# Sheet1.net
KiCad netlist of a schematic drawn in Altium Designer
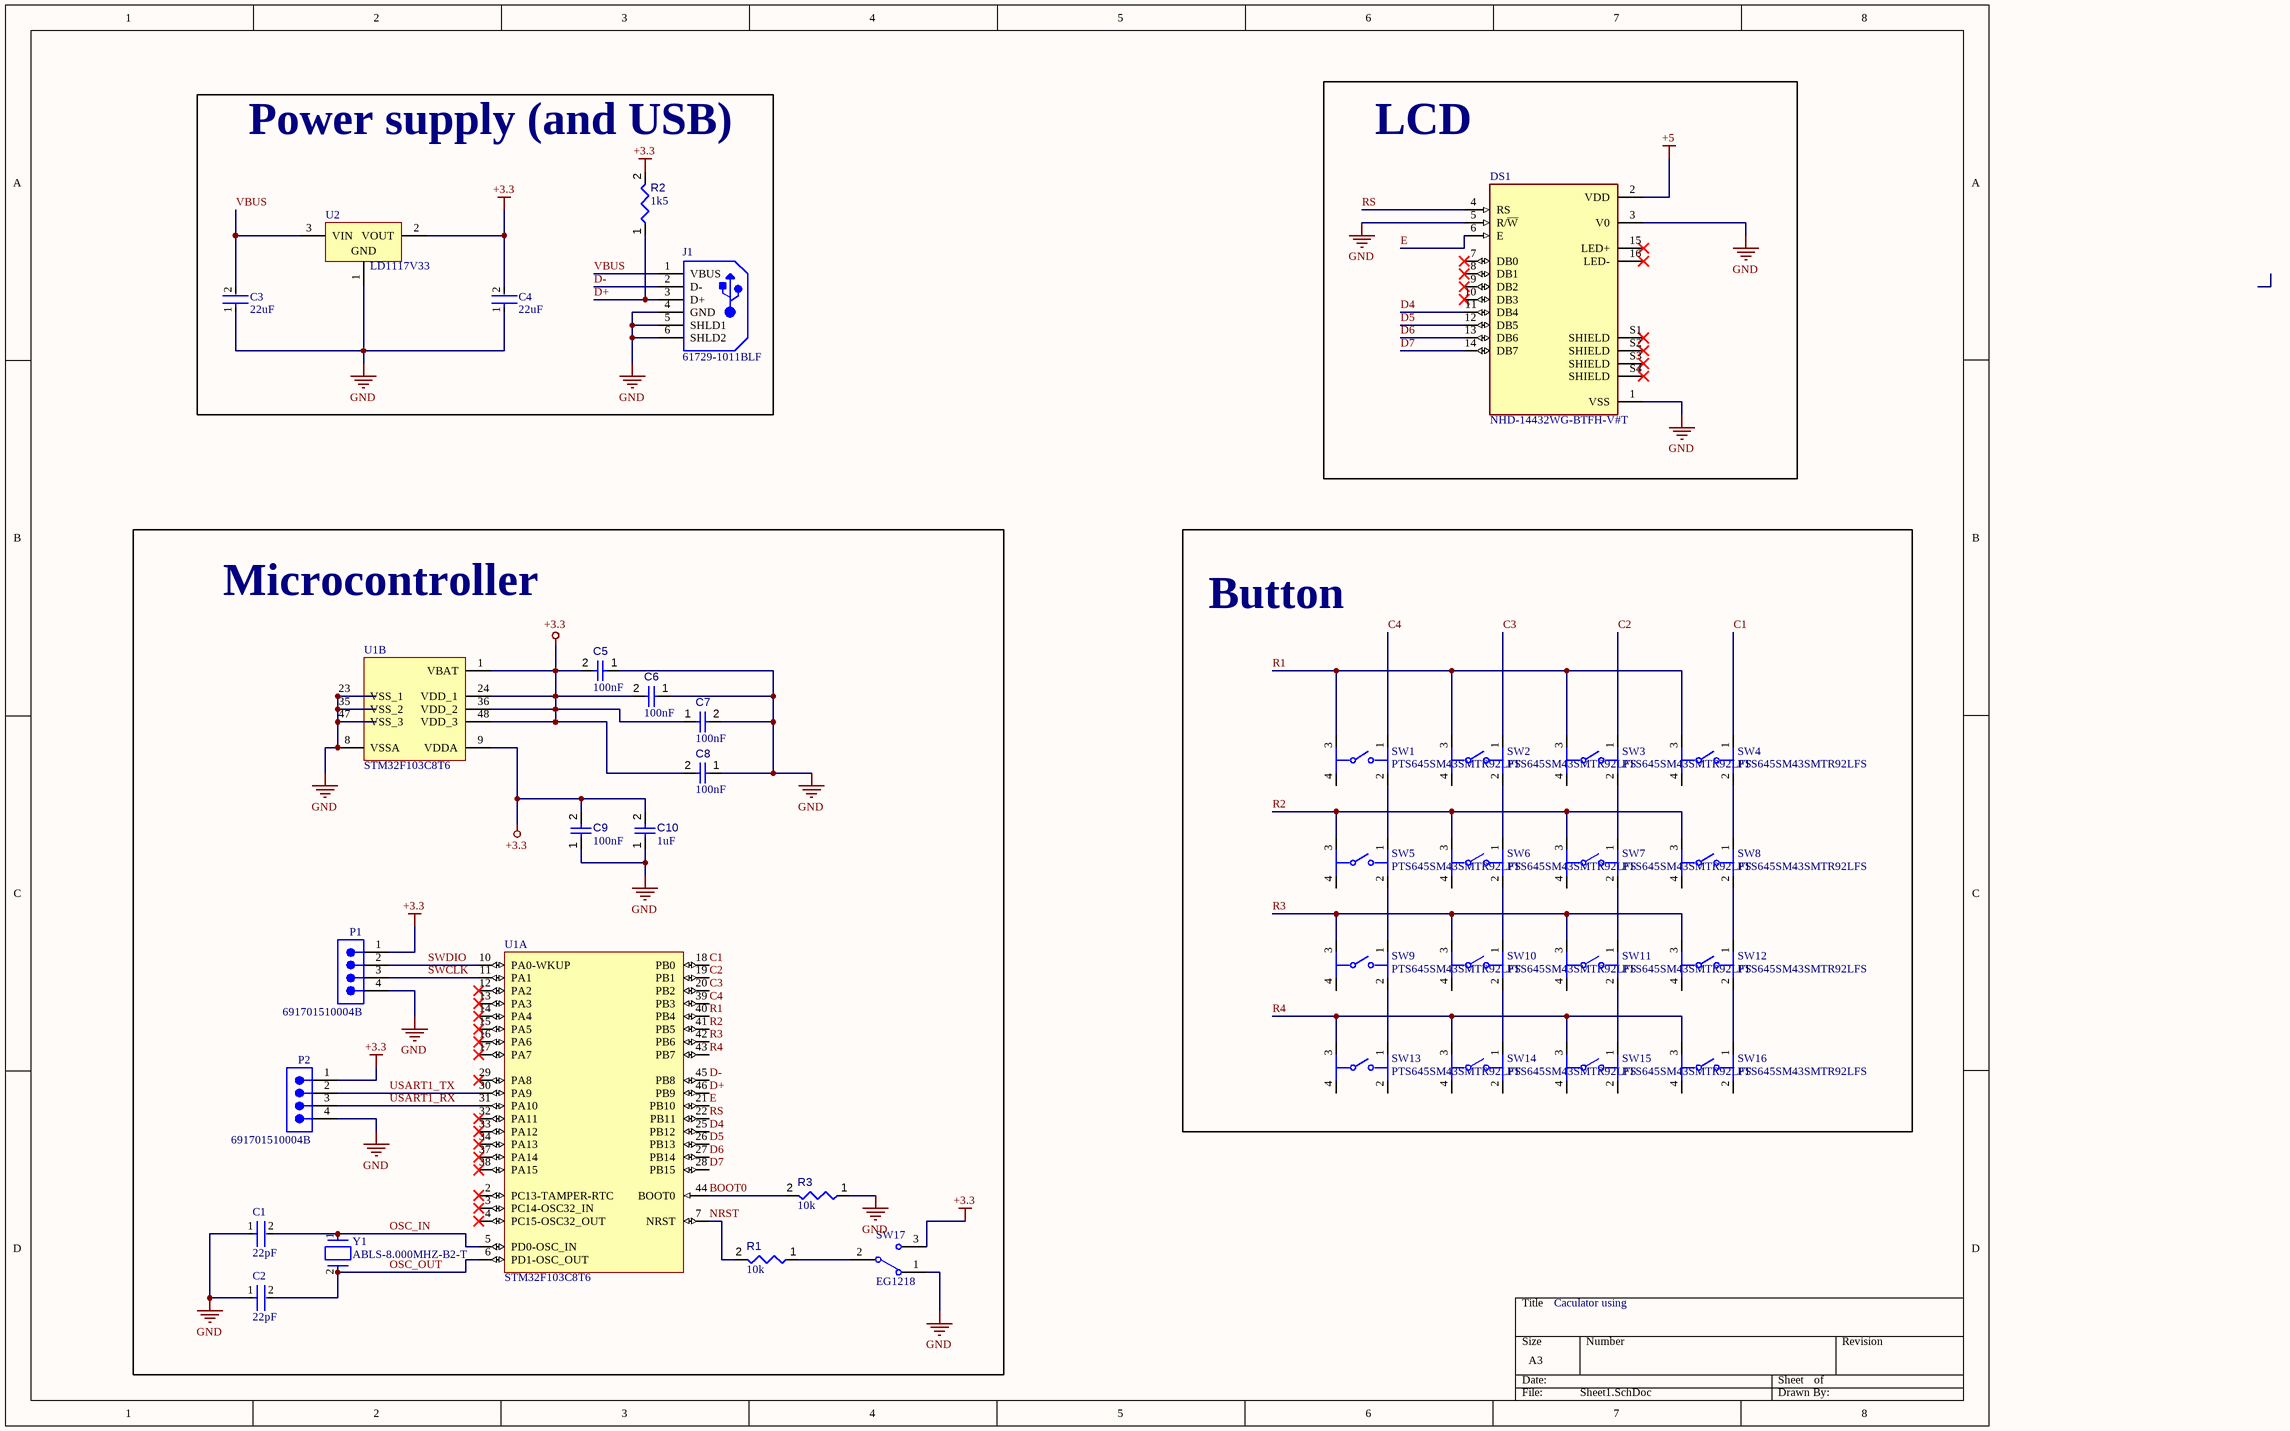
[diagram p0: Sheet1.SchDoc]

(export (version "E")
  (design (tool "Eeschema 10.0.6"))
  (components
    (comp (ref "C1")
      (value "22pF")
      (footprint "FP-RCE0K1-MFG")
      (description "Cap Ceramic 22pF 50V C0G ±5% Radial 5mm +125°C Automotive Bulk")
      (fields (field (name "TOLERANCE") "5%"))
      (libsource (lib "Altium Content Vault") (part "b4654b650e69147ec39a6b967a45e02"))
    )
    (comp (ref "C2")
      (value "22pF")
      (footprint "FP-RCE0K1-MFG")
      (description "Cap Ceramic 22pF 50V C0G ±5% Radial 5mm +125°C Automotive Bulk")
      (fields (field (name "TOLERANCE") "5%"))
      (libsource (lib "Altium Content Vault") (part "b4654b650e69147ec39a6b967a45e02"))
    )
    (comp (ref "C3")
      (value "22uF")
      (footprint "FP-RCE0K1-MFG")
      (description "Cap Ceramic 22pF 50V C0G ±5% Radial 5mm +125°C Automotive Bulk")
      (fields (field (name "TOLERANCE") "5%"))
      (libsource (lib "Altium Content Vault") (part "b4654b650e69147ec39a6b967a45e02"))
    )
    (comp (ref "C4")
      (value "22uF")
      (footprint "FP-RCE0K1-MFG")
      (description "Cap Ceramic 22pF 50V C0G ±5% Radial 5mm +125°C Automotive Bulk")
      (fields (field (name "TOLERANCE") "5%"))
      (libsource (lib "Altium Content Vault") (part "b4654b650e69147ec39a6b967a45e02"))
    )
    (comp (ref "C5")
      (value "100nF")
      (footprint "CAPC1005X56X25LL10T15")
      (description "Chip Capacitor, 0.1 uF, +/- 5%, 16 V, 0402 (1005 Metric)")
      (fields (field (name "TOLERANCE") "5%") (field (name "Comment") "Capacitor 0.1 uF +/- 5% 16 V 0402"))
      (libsource (lib "Nguyen Thaizeroxz") (part "CAP-NP-2"))
    )
    (comp (ref "C6")
      (value "100nF")
      (footprint "CAPC1005X56X25LL10T15")
      (description "Chip Capacitor, 0.1 uF, +/- 5%, 16 V, 0402 (1005 Metric)")
      (fields (field (name "TOLERANCE") "5%") (field (name "Comment") "Capacitor 0.1 uF +/- 5% 16 V 0402"))
      (libsource (lib "Nguyen Thaizeroxz") (part "CAP-NP-2"))
    )
    (comp (ref "C7")
      (value "100nF")
      (footprint "CAPC1005X56X25LL10T15")
      (description "Chip Capacitor, 0.1 uF, +/- 5%, 16 V, 0402 (1005 Metric)")
      (fields (field (name "TOLERANCE") "5%") (field (name "Comment") "Capacitor 0.1 uF +/- 5% 16 V 0402"))
      (libsource (lib "Nguyen Thaizeroxz") (part "CAP-NP-2"))
    )
    (comp (ref "C8")
      (value "100nF")
      (footprint "CAPC1005X56X25LL10T15")
      (description "Chip Capacitor, 0.1 uF, +/- 5%, 16 V, 0402 (1005 Metric)")
      (fields (field (name "TOLERANCE") "5%") (field (name "Comment") "Capacitor 0.1 uF +/- 5% 16 V 0402"))
      (libsource (lib "Nguyen Thaizeroxz") (part "CAP-NP-2"))
    )
    (comp (ref "C9")
      (value "100nF")
      (footprint "CAPC1005X56X25LL10T15")
      (description "Chip Capacitor, 0.1 uF, +/- 5%, 16 V, 0402 (1005 Metric)")
      (fields (field (name "TOLERANCE") "5%") (field (name "Comment") "Capacitor 0.1 uF +/- 5% 16 V 0402"))
      (libsource (lib "Nguyen Thaizeroxz") (part "CAP-NP-2"))
    )
    (comp (ref "C10")
      (value "1uF")
      (footprint "CAPC1005X56X25LL10T15")
      (description "Chip Capacitor, 0.1 uF, +/- 5%, 16 V, 0402 (1005 Metric)")
      (fields (field (name "TOLERANCE") "5%") (field (name "Comment") "Capacitor 0.1 uF +/- 5% 16 V 0402"))
      (libsource (lib "Nguyen Thaizeroxz") (part "CAP-NP-2"))
    )
    (comp (ref "DS1")
      (value "NHD-14432WG-BTFH-V#T")
      (footprint "LCD_NHD-14432WG-BTFH-V#T")
      (fields (field (name "MF") "Newhaven Display"))
      (libsource (lib "Nguyen Thaizeroxz") (part "NHD-14432WG-BTFH-V#T"))
    )
    (comp (ref "J1")
      (value "61729-1011BLF")
      (footprint "FCI-61729-1011BLF_V")
      (description "USB Receptacle B Type, Right Angle, 4 Position, Height 11.5 mm,-40 to 85 degC, RoHS, Tube")
      (fields (field (name "MANUFACTURER") "FCI Electronics"))
      (libsource (lib "Nguyen Thaizeroxz") (part "USB-4-2SHLD"))
    )
    (comp (ref "P1")
      (value "691701510004B")
      (footprint "691701510004B")
      (description "Terminal Block, 5.08MM, Close Vertical Pcb Header, Thr Type, 4 Pins")
      (libsource (lib "Altium Content Vault") (part "TBL - 1R - 04P - Male"))
    )
    (comp (ref "P2")
      (value "691701510004B")
      (footprint "691701510004B")
      (description "Terminal Block, 5.08MM, Close Vertical Pcb Header, Thr Type, 4 Pins")
      (libsource (lib "Altium Content Vault") (part "TBL - 1R - 04P - Male"))
    )
    (comp (ref "R1")
      (value "10k")
      (footprint "RESC0402(1005)_L")
      (description "Chip Resistor, 1 kOhms, +/-5 %, 63 mW, -55 to 155 degC, 0402")
      (fields (field (name "TOLERANCE") "5%") (field (name "POWER") "63mW"))
      (libsource (lib "Nguyen Thaizeroxz") (part "RES-2"))
    )
    (comp (ref "R2")
      (value "1k5")
      (footprint "RESC0402(1005)_L")
      (description "Chip Resistor, 1 kOhms, +/-5 %, 63 mW, -55 to 155 degC, 0402")
      (fields (field (name "TOLERANCE") "5%") (field (name "POWER") "63mW"))
      (libsource (lib "Nguyen Thaizeroxz") (part "RES-2"))
    )
    (comp (ref "R3")
      (value "10k")
      (footprint "RESC0402(1005)_L")
      (description "Chip Resistor, 1 kOhms, +/-5 %, 63 mW, -55 to 155 degC, 0402")
      (fields (field (name "TOLERANCE") "5%") (field (name "POWER") "63mW"))
      (libsource (lib "Nguyen Thaizeroxz") (part "RES-2"))
    )
    (comp (ref "SW1")
      (value "PTS645SM43SMTR92LFS")
      (footprint "FP-PTS645SM43SMTR92LFS-MFG")
      (description "SWITCH TACTILE SPST-NO 0.05A 12V")
      (libsource (lib "Altium Content Vault") (part "1adf0dd01260c80cf25a44bfd6b99ba"))
    )
    (comp (ref "SW2")
      (value "PTS645SM43SMTR92LFS")
      (footprint "FP-PTS645SM43SMTR92LFS-MFG")
      (description "SWITCH TACTILE SPST-NO 0.05A 12V")
      (libsource (lib "Altium Content Vault") (part "1adf0dd01260c80cf25a44bfd6b99ba"))
    )
    (comp (ref "SW3")
      (value "PTS645SM43SMTR92LFS")
      (footprint "FP-PTS645SM43SMTR92LFS-MFG")
      (description "SWITCH TACTILE SPST-NO 0.05A 12V")
      (libsource (lib "Altium Content Vault") (part "1adf0dd01260c80cf25a44bfd6b99ba"))
    )
    (comp (ref "SW4")
      (value "PTS645SM43SMTR92LFS")
      (footprint "FP-PTS645SM43SMTR92LFS-MFG")
      (description "SWITCH TACTILE SPST-NO 0.05A 12V")
      (libsource (lib "Altium Content Vault") (part "1adf0dd01260c80cf25a44bfd6b99ba"))
    )
    (comp (ref "SW5")
      (value "PTS645SM43SMTR92LFS")
      (footprint "FP-PTS645SM43SMTR92LFS-MFG")
      (description "SWITCH TACTILE SPST-NO 0.05A 12V")
      (libsource (lib "Altium Content Vault") (part "1adf0dd01260c80cf25a44bfd6b99ba"))
    )
    (comp (ref "SW6")
      (value "PTS645SM43SMTR92LFS")
      (footprint "FP-PTS645SM43SMTR92LFS-MFG")
      (description "SWITCH TACTILE SPST-NO 0.05A 12V")
      (libsource (lib "Altium Content Vault") (part "1adf0dd01260c80cf25a44bfd6b99ba"))
    )
    (comp (ref "SW7")
      (value "PTS645SM43SMTR92LFS")
      (footprint "FP-PTS645SM43SMTR92LFS-MFG")
      (description "SWITCH TACTILE SPST-NO 0.05A 12V")
      (libsource (lib "Altium Content Vault") (part "1adf0dd01260c80cf25a44bfd6b99ba"))
    )
    (comp (ref "SW8")
      (value "PTS645SM43SMTR92LFS")
      (footprint "FP-PTS645SM43SMTR92LFS-MFG")
      (description "SWITCH TACTILE SPST-NO 0.05A 12V")
      (libsource (lib "Altium Content Vault") (part "1adf0dd01260c80cf25a44bfd6b99ba"))
    )
    (comp (ref "SW9")
      (value "PTS645SM43SMTR92LFS")
      (footprint "FP-PTS645SM43SMTR92LFS-MFG")
      (description "SWITCH TACTILE SPST-NO 0.05A 12V")
      (libsource (lib "Altium Content Vault") (part "1adf0dd01260c80cf25a44bfd6b99ba"))
    )
    (comp (ref "SW10")
      (value "PTS645SM43SMTR92LFS")
      (footprint "FP-PTS645SM43SMTR92LFS-MFG")
      (description "SWITCH TACTILE SPST-NO 0.05A 12V")
      (libsource (lib "Altium Content Vault") (part "1adf0dd01260c80cf25a44bfd6b99ba"))
    )
    (comp (ref "SW11")
      (value "PTS645SM43SMTR92LFS")
      (footprint "FP-PTS645SM43SMTR92LFS-MFG")
      (description "SWITCH TACTILE SPST-NO 0.05A 12V")
      (libsource (lib "Altium Content Vault") (part "1adf0dd01260c80cf25a44bfd6b99ba"))
    )
    (comp (ref "SW12")
      (value "PTS645SM43SMTR92LFS")
      (footprint "FP-PTS645SM43SMTR92LFS-MFG")
      (description "SWITCH TACTILE SPST-NO 0.05A 12V")
      (libsource (lib "Altium Content Vault") (part "1adf0dd01260c80cf25a44bfd6b99ba"))
    )
    (comp (ref "SW13")
      (value "PTS645SM43SMTR92LFS")
      (footprint "FP-PTS645SM43SMTR92LFS-MFG")
      (description "SWITCH TACTILE SPST-NO 0.05A 12V")
      (libsource (lib "Altium Content Vault") (part "1adf0dd01260c80cf25a44bfd6b99ba"))
    )
    (comp (ref "SW14")
      (value "PTS645SM43SMTR92LFS")
      (footprint "FP-PTS645SM43SMTR92LFS-MFG")
      (description "SWITCH TACTILE SPST-NO 0.05A 12V")
      (libsource (lib "Altium Content Vault") (part "1adf0dd01260c80cf25a44bfd6b99ba"))
    )
    (comp (ref "SW15")
      (value "PTS645SM43SMTR92LFS")
      (footprint "FP-PTS645SM43SMTR92LFS-MFG")
      (description "SWITCH TACTILE SPST-NO 0.05A 12V")
      (libsource (lib "Altium Content Vault") (part "1adf0dd01260c80cf25a44bfd6b99ba"))
    )
    (comp (ref "SW16")
      (value "PTS645SM43SMTR92LFS")
      (footprint "FP-PTS645SM43SMTR92LFS-MFG")
      (description "SWITCH TACTILE SPST-NO 0.05A 12V")
      (libsource (lib "Altium Content Vault") (part "1adf0dd01260c80cf25a44bfd6b99ba"))
    )
    (comp (ref "SW17")
      (value "EG1218")
      (footprint "ESWI-EG1218_V")
      (description "Slide Switch, SPDT, 500 V, -20 to 70 degC, 3-Pin THD, RoHS, Bulk")
      (fields (field (name "MANUFACTURER") "E-Switch"))
      (libsource (lib "Nguyen Thaizeroxz") (part "SW-SPDT-3_B"))
    )
    (comp (ref "U1")
      (value "STM32F103C8T6")
      (footprint "STM-LQFP48_M")
      (description "MCU 32-bit STM32F1 ARM Cortex M3 RISC 64KB Flash 2.5V/3.3V 48-Pin LQFP Tray")
      (libsource (lib "Nguyen Thaizeroxz") (part "MC-ARM-STM32F103X8_B-SQ48"))
    )
    (comp (ref "U2")
      (value "LD1117V33")
      (footprint "STM-TO220-3")
      (fields (field (name "MANUFACTURER") "STMicroelectronics") (field (name "POWER") "12W"))
      (libsource (lib "Nguyen Thaizeroxz") (part "STM-LD1117-V33"))
    )
    (comp (ref "Y1")
      (value "ABLS-8.000MHZ-B2-T")
      (footprint "FP-ABLS-MFG")
      (description "CRYSTAL 8.0000MHZ 18PF SMD")
      (fields (field (name "TOLERANCE") "20ppm"))
      (libsource (lib "Altium Content Vault") (part "c23a69dc6c9e2f18f2079038eb95dd1"))
    )
  )
  (nets
    (net (code "1") (name "+3.3") (class "Default")
      (node (ref "C10") (pin "2") (pinfunction "2_2") (pintype "passive"))
      (node (ref "C4") (pin "2") (pinfunction "2_2") (pintype "passive"))
      (node (ref "C5") (pin "2") (pinfunction "2_2") (pintype "passive"))
      (node (ref "C6") (pin "2") (pinfunction "2_2") (pintype "passive"))
      (node (ref "C7") (pin "1") (pinfunction "1_1") (pintype "passive"))
      (node (ref "C8") (pin "2") (pinfunction "2_2") (pintype "passive"))
      (node (ref "C9") (pin "2") (pinfunction "2_2") (pintype "passive"))
      (node (ref "P1") (pin "1") (pinfunction "1_1") (pintype "passive"))
      (node (ref "P2") (pin "1") (pinfunction "1_1") (pintype "passive"))
      (node (ref "R2") (pin "2") (pinfunction "2_2") (pintype "passive"))
      (node (ref "SW17") (pin "3") (pinfunction "3_3") (pintype "passive"))
      (node (ref "U1") (pin "1") (pinfunction "VBAT_1") (pintype "power_in"))
      (node (ref "U1") (pin "24") (pinfunction "VDD_1_24") (pintype "power_in"))
      (node (ref "U1") (pin "36") (pinfunction "VDD_2_36") (pintype "power_in"))
      (node (ref "U1") (pin "48") (pinfunction "VDD_3_48") (pintype "power_in"))
      (node (ref "U1") (pin "9") (pinfunction "VDDA_9") (pintype "power_in"))
      (node (ref "U2") (pin "2") (pinfunction "VOUT_2") (pintype "power_in"))
    )
    (net (code "2") (name "+5") (class "Default")
      (node (ref "DS1") (pin "2") (pinfunction "VDD_2") (pintype "power_in"))
    )
    (net (code "3") (name "/BOOT0") (class "Default")
      (node (ref "R3") (pin "2") (pinfunction "2_2") (pintype "passive"))
      (node (ref "U1") (pin "44") (pinfunction "BOOT0_44") (pintype "input"))
    )
    (net (code "4") (name "/C1") (class "Default")
      (node (ref "SW4") (pin "1") (pinfunction "1_1") (pintype "passive"))
      (node (ref "U1") (pin "18") (pinfunction "PB0_18") (pintype "bidirectional"))
    )
    (net (code "5") (name "/C2") (class "Default")
      (node (ref "SW3") (pin "1") (pinfunction "1_1") (pintype "passive"))
      (node (ref "U1") (pin "19") (pinfunction "PB1_19") (pintype "bidirectional"))
    )
    (net (code "6") (name "/C3") (class "Default")
      (node (ref "SW2") (pin "1") (pinfunction "1_1") (pintype "passive"))
      (node (ref "U1") (pin "20") (pinfunction "PB2_20") (pintype "bidirectional"))
    )
    (net (code "7") (name "/C4") (class "Default")
      (node (ref "SW1") (pin "1") (pinfunction "1_1") (pintype "passive"))
      (node (ref "U1") (pin "39") (pinfunction "PB3_39") (pintype "bidirectional"))
    )
    (net (code "8") (name "/D+") (class "Default")
      (node (ref "J1") (pin "3") (pinfunction "D+_3") (pintype "passive"))
      (node (ref "R2") (pin "1") (pinfunction "1_1") (pintype "passive"))
      (node (ref "U1") (pin "46") (pinfunction "PB9_46") (pintype "bidirectional"))
    )
    (net (code "9") (name "/D-") (class "Default")
      (node (ref "J1") (pin "2") (pinfunction "D-_2") (pintype "passive"))
      (node (ref "U1") (pin "45") (pinfunction "PB8_45") (pintype "bidirectional"))
    )
    (net (code "10") (name "/D4") (class "Default")
      (node (ref "DS1") (pin "11") (pinfunction "DB4_11") (pintype "bidirectional"))
      (node (ref "U1") (pin "25") (pinfunction "PB12_25") (pintype "bidirectional"))
    )
    (net (code "11") (name "/D5") (class "Default")
      (node (ref "DS1") (pin "12") (pinfunction "DB5_12") (pintype "bidirectional"))
      (node (ref "U1") (pin "26") (pinfunction "PB13_26") (pintype "bidirectional"))
    )
    (net (code "12") (name "/D6") (class "Default")
      (node (ref "DS1") (pin "13") (pinfunction "DB6_13") (pintype "bidirectional"))
      (node (ref "U1") (pin "27") (pinfunction "PB14_27") (pintype "bidirectional"))
    )
    (net (code "13") (name "/D7") (class "Default")
      (node (ref "DS1") (pin "14") (pinfunction "DB7_14") (pintype "bidirectional"))
      (node (ref "U1") (pin "28") (pinfunction "PB15_28") (pintype "bidirectional"))
    )
    (net (code "14") (name "/E") (class "Default")
      (node (ref "DS1") (pin "6") (pinfunction "E_6") (pintype "input"))
      (node (ref "U1") (pin "21") (pinfunction "PB10_21") (pintype "bidirectional"))
    )
    (net (code "15") (name "/NRST") (class "Default")
      (node (ref "R1") (pin "2") (pinfunction "2_2") (pintype "passive"))
      (node (ref "U1") (pin "7") (pinfunction "NRST_7") (pintype "bidirectional"))
    )
    (net (code "16") (name "/OSC_IN") (class "Default")
      (node (ref "C1") (pin "2") (pinfunction "2_2") (pintype "passive"))
      (node (ref "U1") (pin "5") (pinfunction "PD0-OSC_IN_5") (pintype "bidirectional"))
      (node (ref "Y1") (pin "1") (pinfunction "1_1") (pintype "passive"))
    )
    (net (code "17") (name "/OSC_OUT") (class "Default")
      (node (ref "C2") (pin "2") (pinfunction "2_2") (pintype "passive"))
      (node (ref "U1") (pin "6") (pinfunction "PD1-OSC_OUT_6") (pintype "bidirectional"))
      (node (ref "Y1") (pin "2") (pinfunction "2_2") (pintype "passive"))
    )
    (net (code "18") (name "/R1") (class "Default")
      (node (ref "SW1") (pin "3") (pinfunction "3_3") (pintype "passive"))
      (node (ref "SW2") (pin "3") (pinfunction "3_3") (pintype "passive"))
      (node (ref "SW3") (pin "3") (pinfunction "3_3") (pintype "passive"))
      (node (ref "SW4") (pin "3") (pinfunction "3_3") (pintype "passive"))
      (node (ref "U1") (pin "40") (pinfunction "PB4_40") (pintype "bidirectional"))
    )
    (net (code "19") (name "/R2") (class "Default")
      (node (ref "SW5") (pin "3") (pinfunction "3_3") (pintype "passive"))
      (node (ref "SW6") (pin "3") (pinfunction "3_3") (pintype "passive"))
      (node (ref "SW7") (pin "3") (pinfunction "3_3") (pintype "passive"))
      (node (ref "SW8") (pin "3") (pinfunction "3_3") (pintype "passive"))
      (node (ref "U1") (pin "41") (pinfunction "PB5_41") (pintype "bidirectional"))
    )
    (net (code "20") (name "/R3") (class "Default")
      (node (ref "SW10") (pin "3") (pinfunction "3_3") (pintype "passive"))
      (node (ref "SW11") (pin "3") (pinfunction "3_3") (pintype "passive"))
      (node (ref "SW12") (pin "3") (pinfunction "3_3") (pintype "passive"))
      (node (ref "SW9") (pin "3") (pinfunction "3_3") (pintype "passive"))
      (node (ref "U1") (pin "42") (pinfunction "PB6_42") (pintype "bidirectional"))
    )
    (net (code "21") (name "/R4") (class "Default")
      (node (ref "SW13") (pin "3") (pinfunction "3_3") (pintype "passive"))
      (node (ref "SW14") (pin "3") (pinfunction "3_3") (pintype "passive"))
      (node (ref "SW15") (pin "3") (pinfunction "3_3") (pintype "passive"))
      (node (ref "SW16") (pin "3") (pinfunction "3_3") (pintype "passive"))
      (node (ref "U1") (pin "43") (pinfunction "PB7_43") (pintype "bidirectional"))
    )
    (net (code "22") (name "/RS") (class "Default")
      (node (ref "DS1") (pin "4") (pinfunction "RS_4") (pintype "input"))
      (node (ref "U1") (pin "22") (pinfunction "PB11_22") (pintype "bidirectional"))
    )
    (net (code "23") (name "/SWCLK") (class "Default")
      (node (ref "P1") (pin "3") (pinfunction "3_3") (pintype "passive"))
      (node (ref "U1") (pin "11") (pinfunction "PA1_11") (pintype "bidirectional"))
    )
    (net (code "24") (name "/SWDIO") (class "Default")
      (node (ref "P1") (pin "2") (pinfunction "2_2") (pintype "passive"))
      (node (ref "U1") (pin "10") (pinfunction "PA0-WKUP_10") (pintype "bidirectional"))
    )
    (net (code "25") (name "/USART1_RX") (class "Default")
      (node (ref "P2") (pin "3") (pinfunction "3_3") (pintype "passive"))
      (node (ref "U1") (pin "31") (pinfunction "PA10_31") (pintype "bidirectional"))
    )
    (net (code "26") (name "/USART1_TX") (class "Default")
      (node (ref "P2") (pin "2") (pinfunction "2_2") (pintype "passive"))
      (node (ref "U1") (pin "30") (pinfunction "PA9_30") (pintype "bidirectional"))
    )
    (net (code "27") (name "/VBUS") (class "Default")
      (node (ref "C3") (pin "2") (pinfunction "2_2") (pintype "passive"))
      (node (ref "J1") (pin "1") (pinfunction "VBUS_1") (pintype "passive"))
      (node (ref "U2") (pin "3") (pinfunction "VIN_3") (pintype "power_in"))
    )
    (net (code "28") (name "GND") (class "Default")
      (node (ref "C1") (pin "1") (pinfunction "1_1") (pintype "passive"))
      (node (ref "C10") (pin "1") (pinfunction "1_1") (pintype "passive"))
      (node (ref "C2") (pin "1") (pinfunction "1_1") (pintype "passive"))
      (node (ref "C3") (pin "1") (pinfunction "1_1") (pintype "passive"))
      (node (ref "C4") (pin "1") (pinfunction "1_1") (pintype "passive"))
      (node (ref "C5") (pin "1") (pinfunction "1_1") (pintype "passive"))
      (node (ref "C6") (pin "1") (pinfunction "1_1") (pintype "passive"))
      (node (ref "C7") (pin "2") (pinfunction "2_2") (pintype "passive"))
      (node (ref "C8") (pin "1") (pinfunction "1_1") (pintype "passive"))
      (node (ref "C9") (pin "1") (pinfunction "1_1") (pintype "passive"))
      (node (ref "DS1") (pin "1") (pinfunction "VSS_1") (pintype "power_in"))
      (node (ref "DS1") (pin "3") (pinfunction "V0_3") (pintype "passive"))
      (node (ref "DS1") (pin "5") (pinfunction "R/~{W}_5") (pintype "input"))
      (node (ref "J1") (pin "4") (pinfunction "GND_4") (pintype "passive"))
      (node (ref "J1") (pin "5") (pinfunction "SHLD1_5") (pintype "passive"))
      (node (ref "J1") (pin "6") (pinfunction "SHLD2_6") (pintype "passive"))
      (node (ref "P1") (pin "4") (pinfunction "4_4") (pintype "passive"))
      (node (ref "P2") (pin "4") (pinfunction "4_4") (pintype "passive"))
      (node (ref "R3") (pin "1") (pinfunction "1_1") (pintype "passive"))
      (node (ref "SW17") (pin "1") (pinfunction "1_1") (pintype "passive"))
      (node (ref "U1") (pin "23") (pinfunction "VSS_1_23") (pintype "power_in"))
      (node (ref "U1") (pin "35") (pinfunction "VSS_2_35") (pintype "power_in"))
      (node (ref "U1") (pin "47") (pinfunction "VSS_3_47") (pintype "power_in"))
      (node (ref "U1") (pin "8") (pinfunction "VSSA_8") (pintype "power_in"))
      (node (ref "U2") (pin "1") (pinfunction "GND_1") (pintype "power_in"))
    )
    (net (code "29") (name "Net-(SW1-Pad2)") (class "Default")
      (node (ref "SW1") (pin "2") (pinfunction "2_2") (pintype "passive"))
      (node (ref "SW5") (pin "1") (pinfunction "1_1") (pintype "passive"))
    )
    (net (code "30") (name "Net-(SW2-Pad2)") (class "Default")
      (node (ref "SW2") (pin "2") (pinfunction "2_2") (pintype "passive"))
      (node (ref "SW6") (pin "1") (pinfunction "1_1") (pintype "passive"))
    )
    (net (code "31") (name "Net-(SW3-Pad2)") (class "Default")
      (node (ref "SW3") (pin "2") (pinfunction "2_2") (pintype "passive"))
      (node (ref "SW7") (pin "1") (pinfunction "1_1") (pintype "passive"))
    )
    (net (code "32") (name "Net-(SW4-Pad2)") (class "Default")
      (node (ref "SW4") (pin "2") (pinfunction "2_2") (pintype "passive"))
      (node (ref "SW8") (pin "1") (pinfunction "1_1") (pintype "passive"))
    )
    (net (code "33") (name "Net-(SW5-Pad2)") (class "Default")
      (node (ref "SW5") (pin "2") (pinfunction "2_2") (pintype "passive"))
      (node (ref "SW9") (pin "1") (pinfunction "1_1") (pintype "passive"))
    )
    (net (code "34") (name "Net-(SW10-Pad1)") (class "Default")
      (node (ref "SW10") (pin "1") (pinfunction "1_1") (pintype "passive"))
      (node (ref "SW6") (pin "2") (pinfunction "2_2") (pintype "passive"))
    )
    (net (code "35") (name "Net-(SW10-Pad2)") (class "Default")
      (node (ref "SW10") (pin "2") (pinfunction "2_2") (pintype "passive"))
      (node (ref "SW14") (pin "1") (pinfunction "1_1") (pintype "passive"))
    )
    (net (code "36") (name "Net-(SW11-Pad1)") (class "Default")
      (node (ref "SW11") (pin "1") (pinfunction "1_1") (pintype "passive"))
      (node (ref "SW7") (pin "2") (pinfunction "2_2") (pintype "passive"))
    )
    (net (code "37") (name "Net-(SW11-Pad2)") (class "Default")
      (node (ref "SW11") (pin "2") (pinfunction "2_2") (pintype "passive"))
      (node (ref "SW15") (pin "1") (pinfunction "1_1") (pintype "passive"))
    )
    (net (code "38") (name "Net-(SW12-Pad1)") (class "Default")
      (node (ref "SW12") (pin "1") (pinfunction "1_1") (pintype "passive"))
      (node (ref "SW8") (pin "2") (pinfunction "2_2") (pintype "passive"))
    )
    (net (code "39") (name "Net-(SW12-Pad2)") (class "Default")
      (node (ref "SW12") (pin "2") (pinfunction "2_2") (pintype "passive"))
      (node (ref "SW16") (pin "1") (pinfunction "1_1") (pintype "passive"))
    )
    (net (code "40") (name "Net-(SW13-Pad1)") (class "Default")
      (node (ref "SW13") (pin "1") (pinfunction "1_1") (pintype "passive"))
      (node (ref "SW9") (pin "2") (pinfunction "2_2") (pintype "passive"))
    )
    (net (code "41") (name "Net-(SW17-COM)") (class "Default")
      (node (ref "R1") (pin "1") (pinfunction "1_1") (pintype "passive"))
      (node (ref "SW17") (pin "2") (pinfunction "COM_2") (pintype "passive"))
    )
    (net (code "42") (name "unconnected-(DS1-DB0-Pad7)") (class "Default")
      (node (ref "DS1") (pin "7") (pinfunction "DB0_7") (pintype "bidirectional+no_connect"))
    )
    (net (code "43") (name "unconnected-(DS1-DB1-Pad8)") (class "Default")
      (node (ref "DS1") (pin "8") (pinfunction "DB1_8") (pintype "bidirectional+no_connect"))
    )
    (net (code "44") (name "unconnected-(DS1-DB2-Pad9)") (class "Default")
      (node (ref "DS1") (pin "9") (pinfunction "DB2_9") (pintype "bidirectional+no_connect"))
    )
    (net (code "45") (name "unconnected-(DS1-DB3-Pad10)") (class "Default")
      (node (ref "DS1") (pin "10") (pinfunction "DB3_10") (pintype "bidirectional+no_connect"))
    )
    (net (code "46") (name "unconnected-(DS1-LED+-Pad15)") (class "Default")
      (node (ref "DS1") (pin "15") (pinfunction "LED+_15") (pintype "passive+no_connect"))
    )
    (net (code "47") (name "unconnected-(DS1-LED--Pad16)") (class "Default")
      (node (ref "DS1") (pin "16") (pinfunction "LED-_16") (pintype "passive+no_connect"))
    )
    (net (code "48") (name "unconnected-(DS1-SHIELD-PadS1)") (class "Default")
      (node (ref "DS1") (pin "S1") (pinfunction "SHIELD_S1") (pintype "passive+no_connect"))
    )
    (net (code "49") (name "unconnected-(DS1-SHIELD-PadS2)") (class "Default")
      (node (ref "DS1") (pin "S2") (pinfunction "SHIELD_S2") (pintype "passive+no_connect"))
    )
    (net (code "50") (name "unconnected-(DS1-SHIELD-PadS3)") (class "Default")
      (node (ref "DS1") (pin "S3") (pinfunction "SHIELD_S3") (pintype "passive+no_connect"))
    )
    (net (code "51") (name "unconnected-(DS1-SHIELD-PadS4)") (class "Default")
      (node (ref "DS1") (pin "S4") (pinfunction "SHIELD_S4") (pintype "passive+no_connect"))
    )
    (net (code "52") (name "unconnected-(SW1-Pad4)") (class "Default")
      (node (ref "SW1") (pin "4") (pinfunction "4_4") (pintype "passive"))
    )
    (net (code "53") (name "unconnected-(SW2-Pad4)") (class "Default")
      (node (ref "SW2") (pin "4") (pinfunction "4_4") (pintype "passive"))
    )
    (net (code "54") (name "unconnected-(SW3-Pad4)") (class "Default")
      (node (ref "SW3") (pin "4") (pinfunction "4_4") (pintype "passive"))
    )
    (net (code "55") (name "unconnected-(SW4-Pad4)") (class "Default")
      (node (ref "SW4") (pin "4") (pinfunction "4_4") (pintype "passive"))
    )
    (net (code "56") (name "unconnected-(SW5-Pad4)") (class "Default")
      (node (ref "SW5") (pin "4") (pinfunction "4_4") (pintype "passive"))
    )
    (net (code "57") (name "unconnected-(SW6-Pad4)") (class "Default")
      (node (ref "SW6") (pin "4") (pinfunction "4_4") (pintype "passive"))
    )
    (net (code "58") (name "unconnected-(SW7-Pad4)") (class "Default")
      (node (ref "SW7") (pin "4") (pinfunction "4_4") (pintype "passive"))
    )
    (net (code "59") (name "unconnected-(SW8-Pad4)") (class "Default")
      (node (ref "SW8") (pin "4") (pinfunction "4_4") (pintype "passive"))
    )
    (net (code "60") (name "unconnected-(SW9-Pad4)") (class "Default")
      (node (ref "SW9") (pin "4") (pinfunction "4_4") (pintype "passive"))
    )
    (net (code "61") (name "unconnected-(SW10-Pad4)") (class "Default")
      (node (ref "SW10") (pin "4") (pinfunction "4_4") (pintype "passive"))
    )
    (net (code "62") (name "unconnected-(SW11-Pad4)") (class "Default")
      (node (ref "SW11") (pin "4") (pinfunction "4_4") (pintype "passive"))
    )
    (net (code "63") (name "unconnected-(SW12-Pad4)") (class "Default")
      (node (ref "SW12") (pin "4") (pinfunction "4_4") (pintype "passive"))
    )
    (net (code "64") (name "unconnected-(SW13-Pad2)") (class "Default")
      (node (ref "SW13") (pin "2") (pinfunction "2_2") (pintype "passive"))
    )
    (net (code "65") (name "unconnected-(SW13-Pad4)") (class "Default")
      (node (ref "SW13") (pin "4") (pinfunction "4_4") (pintype "passive"))
    )
    (net (code "66") (name "unconnected-(SW14-Pad2)") (class "Default")
      (node (ref "SW14") (pin "2") (pinfunction "2_2") (pintype "passive"))
    )
    (net (code "67") (name "unconnected-(SW14-Pad4)") (class "Default")
      (node (ref "SW14") (pin "4") (pinfunction "4_4") (pintype "passive"))
    )
    (net (code "68") (name "unconnected-(SW15-Pad2)") (class "Default")
      (node (ref "SW15") (pin "2") (pinfunction "2_2") (pintype "passive"))
    )
    (net (code "69") (name "unconnected-(SW15-Pad4)") (class "Default")
      (node (ref "SW15") (pin "4") (pinfunction "4_4") (pintype "passive"))
    )
    (net (code "70") (name "unconnected-(SW16-Pad2)") (class "Default")
      (node (ref "SW16") (pin "2") (pinfunction "2_2") (pintype "passive"))
    )
    (net (code "71") (name "unconnected-(SW16-Pad4)") (class "Default")
      (node (ref "SW16") (pin "4") (pinfunction "4_4") (pintype "passive"))
    )
    (net (code "72") (name "unconnected-(U1A-PA2-Pad12)") (class "Default")
      (node (ref "U1") (pin "12") (pinfunction "PA2_12") (pintype "bidirectional+no_connect"))
    )
    (net (code "73") (name "unconnected-(U1A-PA3-Pad13)") (class "Default")
      (node (ref "U1") (pin "13") (pinfunction "PA3_13") (pintype "bidirectional+no_connect"))
    )
    (net (code "74") (name "unconnected-(U1A-PA4-Pad14)") (class "Default")
      (node (ref "U1") (pin "14") (pinfunction "PA4_14") (pintype "bidirectional+no_connect"))
    )
    (net (code "75") (name "unconnected-(U1A-PA5-Pad15)") (class "Default")
      (node (ref "U1") (pin "15") (pinfunction "PA5_15") (pintype "bidirectional+no_connect"))
    )
    (net (code "76") (name "unconnected-(U1A-PA6-Pad16)") (class "Default")
      (node (ref "U1") (pin "16") (pinfunction "PA6_16") (pintype "bidirectional+no_connect"))
    )
    (net (code "77") (name "unconnected-(U1A-PA7-Pad17)") (class "Default")
      (node (ref "U1") (pin "17") (pinfunction "PA7_17") (pintype "bidirectional+no_connect"))
    )
    (net (code "78") (name "unconnected-(U1A-PA8-Pad29)") (class "Default")
      (node (ref "U1") (pin "29") (pinfunction "PA8_29") (pintype "bidirectional+no_connect"))
    )
    (net (code "79") (name "unconnected-(U1A-PA11-Pad32)") (class "Default")
      (node (ref "U1") (pin "32") (pinfunction "PA11_32") (pintype "bidirectional+no_connect"))
    )
    (net (code "80") (name "unconnected-(U1A-PA12-Pad33)") (class "Default")
      (node (ref "U1") (pin "33") (pinfunction "PA12_33") (pintype "bidirectional+no_connect"))
    )
    (net (code "81") (name "unconnected-(U1A-PA13-Pad34)") (class "Default")
      (node (ref "U1") (pin "34") (pinfunction "PA13_34") (pintype "bidirectional+no_connect"))
    )
    (net (code "82") (name "unconnected-(U1A-PA14-Pad37)") (class "Default")
      (node (ref "U1") (pin "37") (pinfunction "PA14_37") (pintype "bidirectional+no_connect"))
    )
    (net (code "83") (name "unconnected-(U1A-PA15-Pad38)") (class "Default")
      (node (ref "U1") (pin "38") (pinfunction "PA15_38") (pintype "bidirectional+no_connect"))
    )
    (net (code "84") (name "unconnected-(U1A-PC13-TAMPER-RTC-Pad2)") (class "Default")
      (node (ref "U1") (pin "2") (pinfunction "PC13-TAMPER-RTC_2") (pintype "bidirectional+no_connect"))
    )
    (net (code "85") (name "unconnected-(U1A-PC14-OSC32_IN-Pad3)") (class "Default")
      (node (ref "U1") (pin "3") (pinfunction "PC14-OSC32_IN_3") (pintype "bidirectional+no_connect"))
    )
    (net (code "86") (name "unconnected-(U1A-PC15-OSC32_OUT-Pad4)") (class "Default")
      (node (ref "U1") (pin "4") (pinfunction "PC15-OSC32_OUT_4") (pintype "bidirectional+no_connect"))
    )
  )
)
